# v3.net
KiCad netlist of a schematic drawn in EAGLE
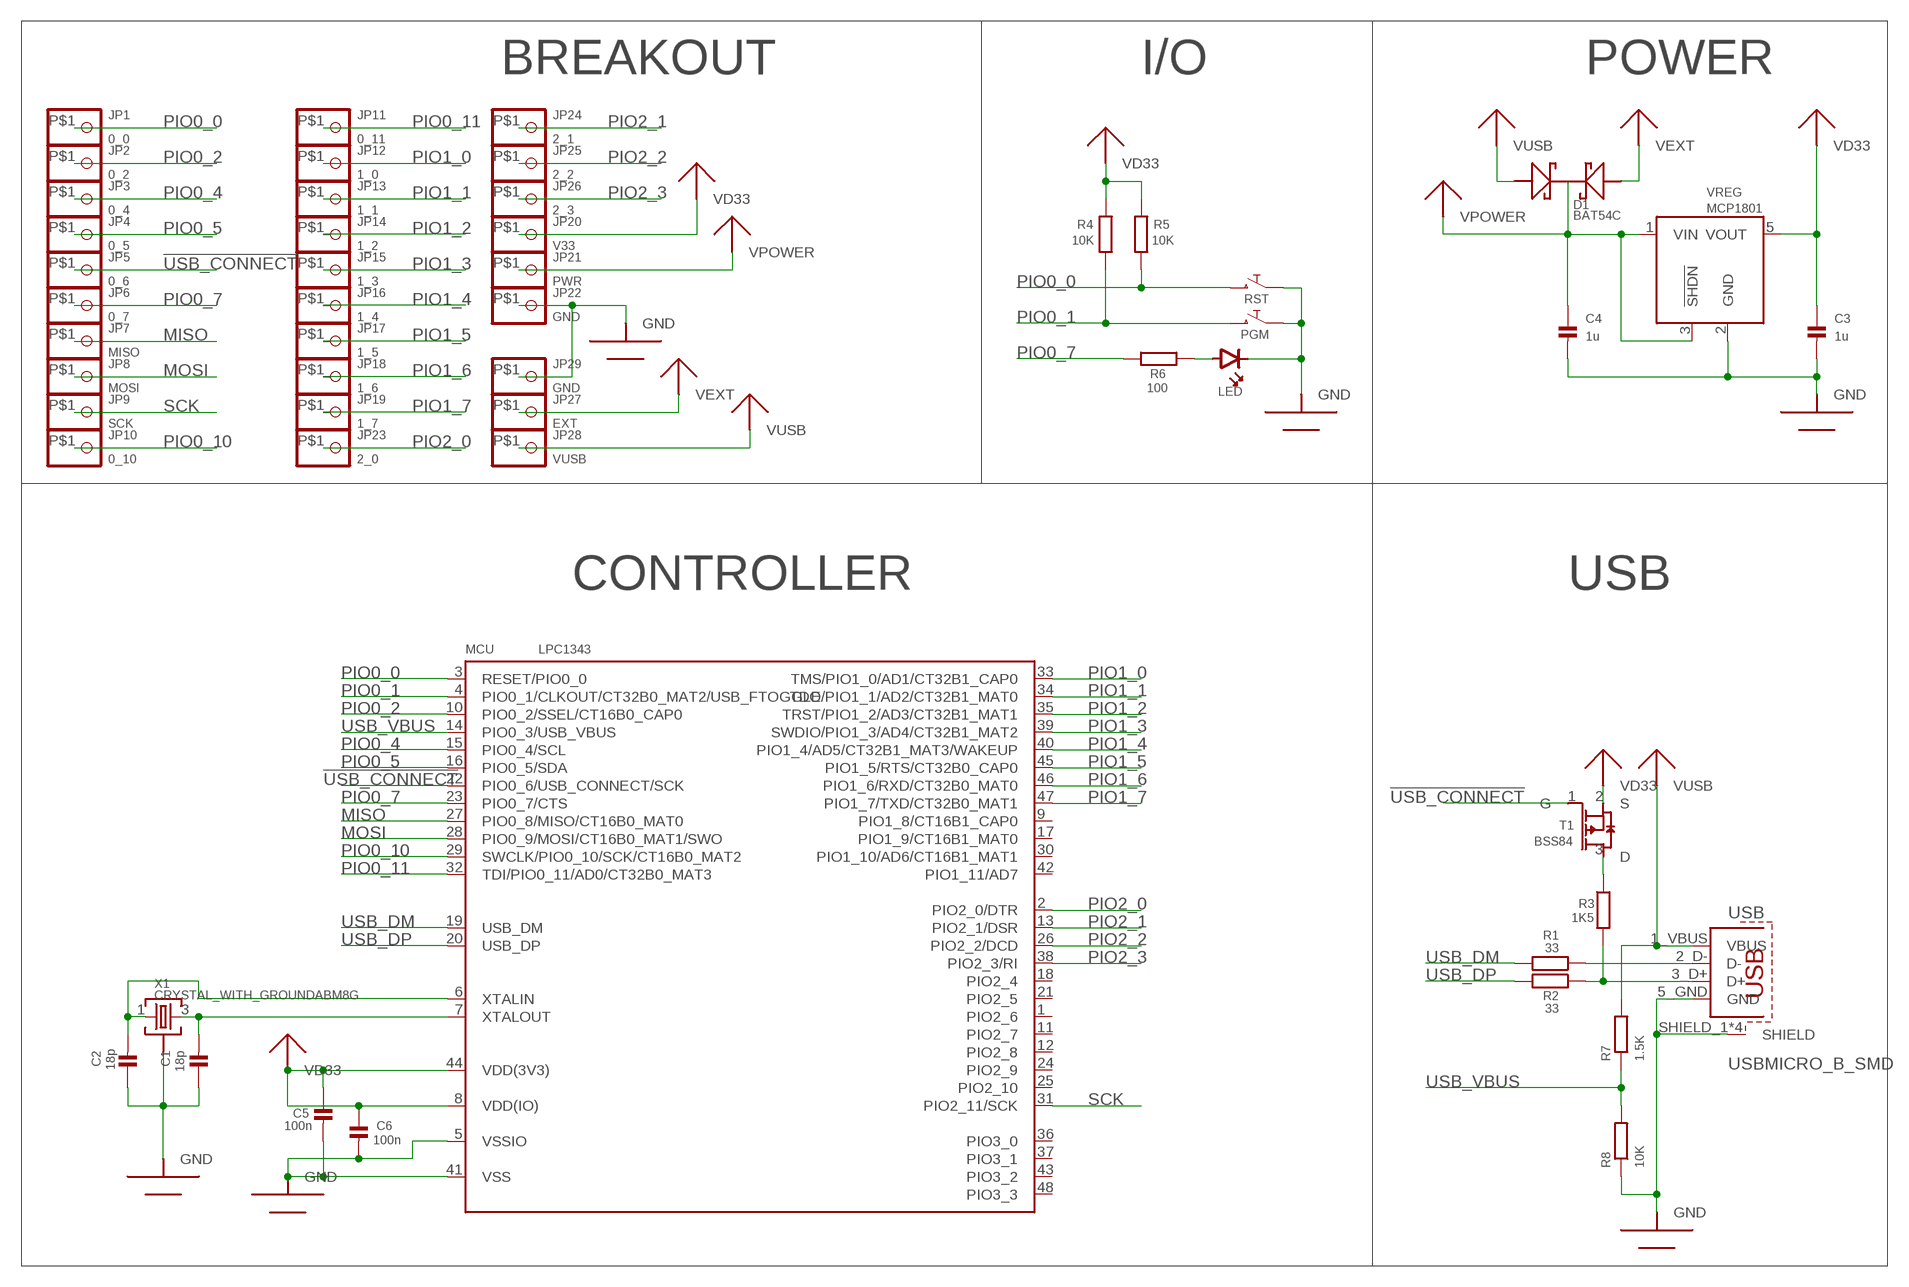
[diagram p0: schematic, sheet 1]

(export (version "E")
  (design (tool "Eeschema 10.0.6"))
  (components
    (comp (ref "C1")
      (value "18p")
      (footprint "eagle-import:0603")
      (libsource (lib "eagle-import") (part "CAP_CERAMIC0603"))
    )
    (comp (ref "C2")
      (value "18p")
      (footprint "eagle-import:0603")
      (libsource (lib "eagle-import") (part "CAP_CERAMIC0603"))
    )
    (comp (ref "C3")
      (value "1u")
      (footprint "eagle-import:0603")
      (libsource (lib "eagle-import") (part "CAP_CERAMIC0603"))
    )
    (comp (ref "C4")
      (value "1u")
      (footprint "eagle-import:0603")
      (libsource (lib "eagle-import") (part "CAP_CERAMIC0603"))
    )
    (comp (ref "C5")
      (value "100n")
      (footprint "eagle-import:0603")
      (libsource (lib "eagle-import") (part "CAP_CERAMIC0603"))
    )
    (comp (ref "C6")
      (value "100n")
      (footprint "eagle-import:0603")
      (libsource (lib "eagle-import") (part "CAP_CERAMIC0603"))
    )
    (comp (ref "D1")
      (value "BAT54C")
      (footprint "eagle-import:SOT323")
      (libsource (lib "eagle-import") (part "BAT54C"))
    )
    (comp (ref "JP1")
      (value "0_0")
      (footprint "eagle-import:PCB_MEDIUM_RECT_PAD")
      (libsource (lib "eagle-import") (part "HEADER-1X1SMD_MEDIUM"))
    )
    (comp (ref "JP2")
      (value "0_2")
      (footprint "eagle-import:PCB_MEDIUM_RECT_PAD")
      (libsource (lib "eagle-import") (part "HEADER-1X1SMD_MEDIUM"))
    )
    (comp (ref "JP3")
      (value "0_4")
      (footprint "eagle-import:PCB_MEDIUM_RECT_PAD")
      (libsource (lib "eagle-import") (part "HEADER-1X1SMD_MEDIUM"))
    )
    (comp (ref "JP4")
      (value "0_5")
      (footprint "eagle-import:PCB_MEDIUM_RECT_PAD")
      (libsource (lib "eagle-import") (part "HEADER-1X1SMD_MEDIUM"))
    )
    (comp (ref "JP5")
      (value "0_6")
      (footprint "eagle-import:PCB_MEDIUM_RECT_PAD")
      (libsource (lib "eagle-import") (part "HEADER-1X1SMD_MEDIUM"))
    )
    (comp (ref "JP6")
      (value "0_7")
      (footprint "eagle-import:PCB_MEDIUM_RECT_PAD")
      (libsource (lib "eagle-import") (part "HEADER-1X1SMD_MEDIUM"))
    )
    (comp (ref "JP7")
      (value "MISO")
      (footprint "eagle-import:PCB_MEDIUM_RECT_PAD")
      (libsource (lib "eagle-import") (part "HEADER-1X1SMD_MEDIUM"))
    )
    (comp (ref "JP8")
      (value "MOSI")
      (footprint "eagle-import:PCB_MEDIUM_RECT_PAD")
      (libsource (lib "eagle-import") (part "HEADER-1X1SMD_MEDIUM"))
    )
    (comp (ref "JP9")
      (value "SCK")
      (footprint "eagle-import:PCB_MEDIUM_RECT_PAD")
      (libsource (lib "eagle-import") (part "HEADER-1X1SMD_MEDIUM"))
    )
    (comp (ref "JP10")
      (value "0_10")
      (footprint "eagle-import:PCB_MEDIUM_RECT_PAD")
      (libsource (lib "eagle-import") (part "HEADER-1X1SMD_MEDIUM"))
    )
    (comp (ref "JP11")
      (value "0_11")
      (footprint "eagle-import:PCB_MEDIUM_RECT_PAD")
      (libsource (lib "eagle-import") (part "HEADER-1X1SMD_MEDIUM"))
    )
    (comp (ref "JP12")
      (value "1_0")
      (footprint "eagle-import:PCB_MEDIUM_RECT_PAD")
      (libsource (lib "eagle-import") (part "HEADER-1X1SMD_MEDIUM"))
    )
    (comp (ref "JP13")
      (value "1_1")
      (footprint "eagle-import:PCB_MEDIUM_RECT_PAD")
      (libsource (lib "eagle-import") (part "HEADER-1X1SMD_MEDIUM"))
    )
    (comp (ref "JP14")
      (value "1_2")
      (footprint "eagle-import:PCB_MEDIUM_RECT_PAD")
      (libsource (lib "eagle-import") (part "HEADER-1X1SMD_MEDIUM"))
    )
    (comp (ref "JP15")
      (value "1_3")
      (footprint "eagle-import:PCB_MEDIUM_RECT_PAD")
      (libsource (lib "eagle-import") (part "HEADER-1X1SMD_MEDIUM"))
    )
    (comp (ref "JP16")
      (value "1_4")
      (footprint "eagle-import:PCB_MEDIUM_RECT_PAD")
      (libsource (lib "eagle-import") (part "HEADER-1X1SMD_MEDIUM"))
    )
    (comp (ref "JP17")
      (value "1_5")
      (footprint "eagle-import:PCB_MEDIUM_RECT_PAD")
      (libsource (lib "eagle-import") (part "HEADER-1X1SMD_MEDIUM"))
    )
    (comp (ref "JP18")
      (value "1_6")
      (footprint "eagle-import:PCB_MEDIUM_RECT_PAD")
      (libsource (lib "eagle-import") (part "HEADER-1X1SMD_MEDIUM"))
    )
    (comp (ref "JP19")
      (value "1_7")
      (footprint "eagle-import:PCB_MEDIUM_RECT_PAD")
      (libsource (lib "eagle-import") (part "HEADER-1X1SMD_MEDIUM"))
    )
    (comp (ref "JP20")
      (value "V33")
      (footprint "eagle-import:PCB_MEDIUM_RECT_PAD")
      (libsource (lib "eagle-import") (part "HEADER-1X1SMD_MEDIUM"))
    )
    (comp (ref "JP21")
      (value "PWR")
      (footprint "eagle-import:PCB_MEDIUM_RECT_PAD")
      (libsource (lib "eagle-import") (part "HEADER-1X1SMD_MEDIUM"))
    )
    (comp (ref "JP22")
      (value "GND")
      (footprint "eagle-import:PCB_MEDIUM_RECT_PAD")
      (libsource (lib "eagle-import") (part "HEADER-1X1SMD_MEDIUM"))
    )
    (comp (ref "JP23")
      (value "2_0")
      (footprint "eagle-import:PCB_MEDIUM_RECT_PAD")
      (libsource (lib "eagle-import") (part "HEADER-1X1SMD_MEDIUM"))
    )
    (comp (ref "JP24")
      (value "2_1")
      (footprint "eagle-import:PCB_MEDIUM_RECT_PAD")
      (libsource (lib "eagle-import") (part "HEADER-1X1SMD_MEDIUM"))
    )
    (comp (ref "JP25")
      (value "2_2")
      (footprint "eagle-import:PCB_MEDIUM_RECT_PAD")
      (libsource (lib "eagle-import") (part "HEADER-1X1SMD_MEDIUM"))
    )
    (comp (ref "JP26")
      (value "2_3")
      (footprint "eagle-import:PCB_MEDIUM_RECT_PAD")
      (libsource (lib "eagle-import") (part "HEADER-1X1SMD_MEDIUM"))
    )
    (comp (ref "JP27")
      (value "EXT")
      (footprint "eagle-import:PCB_LARGER_RECT_PAD")
      (libsource (lib "eagle-import") (part "HEADER-1X1SMD_LARGER"))
    )
    (comp (ref "JP28")
      (value "VUSB")
      (footprint "eagle-import:PCB_LARGER_RECT_PAD")
      (libsource (lib "eagle-import") (part "HEADER-1X1SMD_LARGER"))
    )
    (comp (ref "JP29")
      (value "GND")
      (footprint "eagle-import:PCB_LARGER_RECT_PAD")
      (libsource (lib "eagle-import") (part "HEADER-1X1SMD_LARGER"))
    )
    (comp (ref "LED")
      (value "LED0603")
      (footprint "eagle-import:0603_POLAR")
      (libsource (lib "eagle-import") (part "LED0603"))
    )
    (comp (ref "MCU")
      (value "LPC1343")
      (footprint "eagle-import:LQFP48")
      (libsource (lib "eagle-import") (part "LPC1343_QFP"))
    )
    (comp (ref "PGM")
      (value "PUSHBUTTONKMR2XX")
      (footprint "eagle-import:CK-KMR2")
      (libsource (lib "eagle-import") (part "PUSHBUTTONKMR2XX"))
    )
    (comp (ref "R1")
      (value "33")
      (footprint "eagle-import:0603")
      (libsource (lib "eagle-import") (part "R-EU_0603"))
    )
    (comp (ref "R2")
      (value "33")
      (footprint "eagle-import:0603")
      (libsource (lib "eagle-import") (part "R-EU_0603"))
    )
    (comp (ref "R3")
      (value "1K5")
      (footprint "eagle-import:0603")
      (libsource (lib "eagle-import") (part "R-EU_0603"))
    )
    (comp (ref "R4")
      (value "10K")
      (footprint "eagle-import:0603")
      (libsource (lib "eagle-import") (part "R-EU_0603"))
    )
    (comp (ref "R5")
      (value "10K")
      (footprint "eagle-import:0603")
      (libsource (lib "eagle-import") (part "R-EU_0603"))
    )
    (comp (ref "R6")
      (value "100")
      (footprint "eagle-import:0603")
      (libsource (lib "eagle-import") (part "R-EU_0603"))
    )
    (comp (ref "R7")
      (value "1.5K")
      (footprint "eagle-import:0603")
      (libsource (lib "eagle-import") (part "R-EU_0603"))
    )
    (comp (ref "R8")
      (value "10K")
      (footprint "eagle-import:0603")
      (libsource (lib "eagle-import") (part "R-EU_0603"))
    )
    (comp (ref "RST")
      (value "PUSHBUTTONKMR2XX")
      (footprint "eagle-import:CK-KMR2")
      (libsource (lib "eagle-import") (part "PUSHBUTTONKMR2XX"))
    )
    (comp (ref "T1")
      (value "BSS84")
      (footprint "eagle-import:SOT23")
      (libsource (lib "eagle-import") (part "PMOS_ENH"))
    )
    (comp (ref "USB")
      (value "USBMICRO_B_SMD")
      (footprint "eagle-import:MICRO_USB_B_SMD")
      (libsource (lib "eagle-import") (part "USBMICRO_B_SMD"))
    )
    (comp (ref "VREG")
      (value "MCP1801")
      (footprint "eagle-import:SOT-23-5")
      (libsource (lib "eagle-import") (part "MCP180XSOT-23-5"))
    )
    (comp (ref "X1")
      (value "CRYSTAL_WITH_GROUNDABM8G")
      (footprint "eagle-import:ABM8G")
      (libsource (lib "eagle-import") (part "CRYSTAL_WITH_GROUNDABM8G"))
    )
  )
  (nets
    (net (code "1") (name "/MISO") (class "Default")
      (node (ref "JP7") (pin "P$1") (pinfunction "1_P$1") (pintype "passive"))
      (node (ref "MCU") (pin "27") (pinfunction "PIO0_8/MISO/CT16B0_MAT0_27") (pintype "bidirectional"))
    )
    (net (code "2") (name "/MOSI") (class "Default")
      (node (ref "JP8") (pin "P$1") (pinfunction "1_P$1") (pintype "passive"))
      (node (ref "MCU") (pin "28") (pinfunction "PIO0_9/MOSI/CT16B0_MAT1/SWO_28") (pintype "bidirectional"))
    )
    (net (code "3") (name "/PIO0_0") (class "Default")
      (node (ref "JP1") (pin "P$1") (pinfunction "1_P$1") (pintype "passive"))
      (node (ref "MCU") (pin "3") (pinfunction "RESET/PIO0_0_3") (pintype "bidirectional"))
      (node (ref "R5") (pin "1") (pinfunction "1_1") (pintype "passive"))
      (node (ref "RST") (pin "P$3") (pinfunction "2_P$3") (pintype "bidirectional"))
      (node (ref "RST") (pin "P$4") (pinfunction "2_P$4") (pintype "bidirectional"))
    )
    (net (code "4") (name "/PIO0_1") (class "Default")
      (node (ref "MCU") (pin "4") (pinfunction "PIO0_1/CLKOUT/CT32B0_MAT2/USB_FTOGGLE_4") (pintype "bidirectional"))
      (node (ref "PGM") (pin "P$3") (pinfunction "2_P$3") (pintype "bidirectional"))
      (node (ref "PGM") (pin "P$4") (pinfunction "2_P$4") (pintype "bidirectional"))
      (node (ref "R4") (pin "1") (pinfunction "1_1") (pintype "passive"))
    )
    (net (code "5") (name "/PIO0_2") (class "Default")
      (node (ref "JP2") (pin "P$1") (pinfunction "1_P$1") (pintype "passive"))
      (node (ref "MCU") (pin "10") (pinfunction "PIO0_2/SSEL/CT16B0_CAP0_10") (pintype "bidirectional"))
    )
    (net (code "6") (name "/PIO0_4") (class "Default")
      (node (ref "JP3") (pin "P$1") (pinfunction "1_P$1") (pintype "passive"))
      (node (ref "MCU") (pin "15") (pinfunction "PIO0_4/SCL_15") (pintype "bidirectional"))
    )
    (net (code "7") (name "/PIO0_5") (class "Default")
      (node (ref "JP4") (pin "P$1") (pinfunction "1_P$1") (pintype "passive"))
      (node (ref "MCU") (pin "16") (pinfunction "PIO0_5/SDA_16") (pintype "bidirectional"))
    )
    (net (code "8") (name "/PIO0_7") (class "Default")
      (node (ref "JP6") (pin "P$1") (pinfunction "1_P$1") (pintype "passive"))
      (node (ref "MCU") (pin "23") (pinfunction "PIO0_7/CTS_23") (pintype "bidirectional"))
      (node (ref "R6") (pin "2") (pinfunction "2_2") (pintype "passive"))
    )
    (net (code "9") (name "/PIO0_10") (class "Default")
      (node (ref "JP10") (pin "P$1") (pinfunction "1_P$1") (pintype "passive"))
      (node (ref "MCU") (pin "29") (pinfunction "SWCLK/PIO0_10/SCK/CT16B0_MAT2_29") (pintype "bidirectional"))
    )
    (net (code "10") (name "/PIO0_11") (class "Default")
      (node (ref "JP11") (pin "P$1") (pinfunction "1_P$1") (pintype "passive"))
      (node (ref "MCU") (pin "32") (pinfunction "TDI/PIO0_11/AD0/CT32B0_MAT3_32") (pintype "bidirectional"))
    )
    (net (code "11") (name "/PIO1_0") (class "Default")
      (node (ref "JP12") (pin "P$1") (pinfunction "1_P$1") (pintype "passive"))
      (node (ref "MCU") (pin "33") (pinfunction "TMS/PIO1_0/AD1/CT32B1_CAP0_33") (pintype "bidirectional"))
    )
    (net (code "12") (name "/PIO1_1") (class "Default")
      (node (ref "JP13") (pin "P$1") (pinfunction "1_P$1") (pintype "passive"))
      (node (ref "MCU") (pin "34") (pinfunction "TDO/PIO1_1/AD2/CT32B1_MAT0_34") (pintype "bidirectional"))
    )
    (net (code "13") (name "/PIO1_2") (class "Default")
      (node (ref "JP14") (pin "P$1") (pinfunction "1_P$1") (pintype "passive"))
      (node (ref "MCU") (pin "35") (pinfunction "TRST/PIO1_2/AD3/CT32B1_MAT1_35") (pintype "bidirectional"))
    )
    (net (code "14") (name "/PIO1_3") (class "Default")
      (node (ref "JP15") (pin "P$1") (pinfunction "1_P$1") (pintype "passive"))
      (node (ref "MCU") (pin "39") (pinfunction "SWDIO/PIO1_3/AD4/CT32B1_MAT2_39") (pintype "bidirectional"))
    )
    (net (code "15") (name "/PIO1_4") (class "Default")
      (node (ref "JP16") (pin "P$1") (pinfunction "1_P$1") (pintype "passive"))
      (node (ref "MCU") (pin "40") (pinfunction "PIO1_4/AD5/CT32B1_MAT3/WAKEUP_40") (pintype "bidirectional"))
    )
    (net (code "16") (name "/PIO1_5") (class "Default")
      (node (ref "JP17") (pin "P$1") (pinfunction "1_P$1") (pintype "passive"))
      (node (ref "MCU") (pin "45") (pinfunction "PIO1_5/RTS/CT32B0_CAP0_45") (pintype "bidirectional"))
    )
    (net (code "17") (name "/PIO1_6") (class "Default")
      (node (ref "JP18") (pin "P$1") (pinfunction "1_P$1") (pintype "passive"))
      (node (ref "MCU") (pin "46") (pinfunction "PIO1_6/RXD/CT32B0_MAT0_46") (pintype "bidirectional"))
    )
    (net (code "18") (name "/PIO1_7") (class "Default")
      (node (ref "JP19") (pin "P$1") (pinfunction "1_P$1") (pintype "passive"))
      (node (ref "MCU") (pin "47") (pinfunction "PIO1_7/TXD/CT32B0_MAT1_47") (pintype "bidirectional"))
    )
    (net (code "19") (name "/PIO2_0") (class "Default")
      (node (ref "JP23") (pin "P$1") (pinfunction "1_P$1") (pintype "passive"))
      (node (ref "MCU") (pin "2") (pinfunction "PIO2_0/DTR_2") (pintype "bidirectional"))
    )
    (net (code "20") (name "/PIO2_1") (class "Default")
      (node (ref "JP24") (pin "P$1") (pinfunction "1_P$1") (pintype "passive"))
      (node (ref "MCU") (pin "13") (pinfunction "PIO2_1/DSR_13") (pintype "bidirectional"))
    )
    (net (code "21") (name "/PIO2_2") (class "Default")
      (node (ref "JP25") (pin "P$1") (pinfunction "1_P$1") (pintype "passive"))
      (node (ref "MCU") (pin "26") (pinfunction "PIO2_2/DCD_26") (pintype "bidirectional"))
    )
    (net (code "22") (name "/PIO2_3") (class "Default")
      (node (ref "JP26") (pin "P$1") (pinfunction "1_P$1") (pintype "passive"))
      (node (ref "MCU") (pin "38") (pinfunction "PIO2_3/RI_38") (pintype "bidirectional"))
    )
    (net (code "23") (name "/SCK") (class "Default")
      (node (ref "JP9") (pin "P$1") (pinfunction "1_P$1") (pintype "passive"))
      (node (ref "MCU") (pin "31") (pinfunction "PIO2_11/SCK_31") (pintype "bidirectional"))
    )
    (net (code "24") (name "/USB_DM") (class "Default")
      (node (ref "MCU") (pin "19") (pinfunction "USB_DM_19") (pintype "bidirectional"))
      (node (ref "R1") (pin "2") (pinfunction "2_2") (pintype "passive"))
    )
    (net (code "25") (name "/USB_DP") (class "Default")
      (node (ref "MCU") (pin "20") (pinfunction "USB_DP_20") (pintype "bidirectional"))
      (node (ref "R2") (pin "2") (pinfunction "2_2") (pintype "passive"))
    )
    (net (code "26") (name "/USB_VBUS") (class "Default")
      (node (ref "MCU") (pin "14") (pinfunction "PIO0_3/USB_VBUS_14") (pintype "bidirectional"))
      (node (ref "R7") (pin "1") (pinfunction "1_1") (pintype "passive"))
      (node (ref "R8") (pin "2") (pinfunction "2_2") (pintype "passive"))
    )
    (net (code "27") (name "/~{USB_CONNECT}") (class "Default")
      (node (ref "JP5") (pin "P$1") (pinfunction "1_P$1") (pintype "passive"))
      (node (ref "MCU") (pin "22") (pinfunction "PIO0_6/USB_CONNECT/SCK_22") (pintype "bidirectional"))
      (node (ref "T1") (pin "1") (pinfunction "G_1") (pintype "bidirectional"))
    )
    (net (code "28") (name "GND") (class "Default")
      (node (ref "C1") (pin "1") (pinfunction "P$1_1") (pintype "passive"))
      (node (ref "C2") (pin "1") (pinfunction "P$1_1") (pintype "passive"))
      (node (ref "C3") (pin "2") (pinfunction "P$2_2") (pintype "passive"))
      (node (ref "C4") (pin "2") (pinfunction "P$2_2") (pintype "passive"))
      (node (ref "C5") (pin "2") (pinfunction "P$2_2") (pintype "passive"))
      (node (ref "C6") (pin "2") (pinfunction "P$2_2") (pintype "passive"))
      (node (ref "JP22") (pin "P$1") (pinfunction "1_P$1") (pintype "passive"))
      (node (ref "JP29") (pin "P$1") (pinfunction "1_P$1") (pintype "passive"))
      (node (ref "LED") (pin "K") (pinfunction "CATHODE_K") (pintype "bidirectional"))
      (node (ref "MCU") (pin "41") (pinfunction "VSS_41") (pintype "power_in"))
      (node (ref "MCU") (pin "5") (pinfunction "VSSIO_5") (pintype "power_in"))
      (node (ref "PGM") (pin "P$1") (pinfunction "1_P$1") (pintype "bidirectional"))
      (node (ref "PGM") (pin "P$2") (pinfunction "1_P$2") (pintype "bidirectional"))
      (node (ref "R8") (pin "1") (pinfunction "1_1") (pintype "passive"))
      (node (ref "RST") (pin "P$1") (pinfunction "1_P$1") (pintype "bidirectional"))
      (node (ref "RST") (pin "P$2") (pinfunction "1_P$2") (pintype "bidirectional"))
      (node (ref "USB") (pin "5_GND") (pinfunction "GND_5_GND") (pintype "power_in"))
      (node (ref "USB") (pin "SHIELD_1") (pinfunction "SHIELD_SHIELD_1") (pintype "passive"))
      (node (ref "USB") (pin "SHIELD_2") (pinfunction "SHIELD_SHIELD_2") (pintype "passive"))
      (node (ref "USB") (pin "SHIELD_3") (pinfunction "SHIELD_SHIELD_3") (pintype "passive"))
      (node (ref "USB") (pin "SHIELD_4") (pinfunction "SHIELD_SHIELD_4") (pintype "passive"))
      (node (ref "VREG") (pin "2") (pinfunction "GND_2") (pintype "power_in"))
      (node (ref "X1") (pin "2") (pinfunction "GND_2") (pintype "power_in"))
      (node (ref "X1") (pin "4") (pinfunction "GND_4") (pintype "power_in"))
    )
    (net (code "29") (name "Net-(C1-P$2)") (class "Default")
      (node (ref "C1") (pin "2") (pinfunction "P$2_2") (pintype "passive"))
      (node (ref "MCU") (pin "7") (pinfunction "XTALOUT_7") (pintype "output"))
      (node (ref "X1") (pin "3") (pinfunction "2_3") (pintype "passive"))
    )
    (net (code "30") (name "Net-(C2-P$2)") (class "Default")
      (node (ref "C2") (pin "2") (pinfunction "P$2_2") (pintype "passive"))
      (node (ref "MCU") (pin "6") (pinfunction "XTALIN_6") (pintype "input"))
      (node (ref "X1") (pin "1") (pinfunction "1_1") (pintype "passive"))
    )
    (net (code "31") (name "Net-(LED-ANODE)") (class "Default")
      (node (ref "LED") (pin "A") (pinfunction "ANODE_A") (pintype "bidirectional"))
      (node (ref "R6") (pin "1") (pinfunction "1_1") (pintype "passive"))
    )
    (net (code "32") (name "Net-(T1-D)") (class "Default")
      (node (ref "R3") (pin "1") (pinfunction "1_1") (pintype "passive"))
      (node (ref "T1") (pin "3") (pinfunction "D_3") (pintype "bidirectional"))
    )
    (net (code "33") (name "Net-(USB-D+)") (class "Default")
      (node (ref "R2") (pin "1") (pinfunction "1_1") (pintype "passive"))
      (node (ref "R3") (pin "2") (pinfunction "2_2") (pintype "passive"))
      (node (ref "USB") (pin "3_D+") (pinfunction "D+_3_D+") (pintype "bidirectional"))
    )
    (net (code "34") (name "Net-(USB-D-)") (class "Default")
      (node (ref "R1") (pin "1") (pinfunction "1_1") (pintype "passive"))
      (node (ref "USB") (pin "2_D-") (pinfunction "D-_2_D-") (pintype "bidirectional"))
    )
    (net (code "35") (name "VD33") (class "Default")
      (node (ref "C3") (pin "1") (pinfunction "P$1_1") (pintype "passive"))
      (node (ref "C5") (pin "1") (pinfunction "P$1_1") (pintype "passive"))
      (node (ref "C6") (pin "1") (pinfunction "P$1_1") (pintype "passive"))
      (node (ref "JP20") (pin "P$1") (pinfunction "1_P$1") (pintype "passive"))
      (node (ref "MCU") (pin "44") (pinfunction "VDD(3V3)_44") (pintype "power_in"))
      (node (ref "MCU") (pin "8") (pinfunction "VDD(IO)_8") (pintype "power_in"))
      (node (ref "R4") (pin "2") (pinfunction "2_2") (pintype "passive"))
      (node (ref "R5") (pin "2") (pinfunction "2_2") (pintype "passive"))
      (node (ref "T1") (pin "2") (pinfunction "S_2") (pintype "bidirectional"))
      (node (ref "VREG") (pin "5") (pinfunction "VOUT_5") (pintype "power_in"))
    )
    (net (code "36") (name "VEXT") (class "Default")
      (node (ref "D1") (pin "2") (pinfunction "ANODE2_2") (pintype "bidirectional"))
      (node (ref "JP27") (pin "P$1") (pinfunction "1_P$1") (pintype "passive"))
    )
    (net (code "37") (name "VPOWER") (class "Default")
      (node (ref "C4") (pin "1") (pinfunction "P$1_1") (pintype "passive"))
      (node (ref "D1") (pin "3") (pinfunction "CATHODE_3") (pintype "bidirectional"))
      (node (ref "JP21") (pin "P$1") (pinfunction "1_P$1") (pintype "passive"))
      (node (ref "VREG") (pin "1") (pinfunction "VIN_1") (pintype "power_in"))
      (node (ref "VREG") (pin "3") (pinfunction "~{SHDN}_3") (pintype "input"))
    )
    (net (code "38") (name "VUSB") (class "Default")
      (node (ref "D1") (pin "1") (pinfunction "ANODE1_1") (pintype "bidirectional"))
      (node (ref "JP28") (pin "P$1") (pinfunction "1_P$1") (pintype "passive"))
      (node (ref "R7") (pin "2") (pinfunction "2_2") (pintype "passive"))
      (node (ref "USB") (pin "1_VBUS") (pinfunction "VBUS_1_VBUS") (pintype "power_in"))
    )
    (net (code "39") (name "unconnected-(MCU-PIO1_8{slash}CT16B1_CAP0-Pad9)") (class "Default")
      (node (ref "MCU") (pin "9") (pinfunction "PIO1_8/CT16B1_CAP0_9") (pintype "bidirectional"))
    )
    (net (code "40") (name "unconnected-(MCU-PIO1_9{slash}CT16B1_MAT0-Pad17)") (class "Default")
      (node (ref "MCU") (pin "17") (pinfunction "PIO1_9/CT16B1_MAT0_17") (pintype "bidirectional"))
    )
    (net (code "41") (name "unconnected-(MCU-PIO1_10{slash}AD6{slash}CT16B1_MAT1-Pad30)") (class "Default")
      (node (ref "MCU") (pin "30") (pinfunction "PIO1_10/AD6/CT16B1_MAT1_30") (pintype "bidirectional"))
    )
    (net (code "42") (name "unconnected-(MCU-PIO1_11{slash}AD7-Pad42)") (class "Default")
      (node (ref "MCU") (pin "42") (pinfunction "PIO1_11/AD7_42") (pintype "bidirectional"))
    )
    (net (code "43") (name "unconnected-(MCU-PIO2_4-Pad18)") (class "Default")
      (node (ref "MCU") (pin "18") (pinfunction "PIO2_4_18") (pintype "bidirectional"))
    )
    (net (code "44") (name "unconnected-(MCU-PIO2_5-Pad21)") (class "Default")
      (node (ref "MCU") (pin "21") (pinfunction "PIO2_5_21") (pintype "bidirectional"))
    )
    (net (code "45") (name "unconnected-(MCU-PIO2_6-Pad1)") (class "Default")
      (node (ref "MCU") (pin "1") (pinfunction "PIO2_6_1") (pintype "bidirectional"))
    )
    (net (code "46") (name "unconnected-(MCU-PIO2_7-Pad11)") (class "Default")
      (node (ref "MCU") (pin "11") (pinfunction "PIO2_7_11") (pintype "bidirectional"))
    )
    (net (code "47") (name "unconnected-(MCU-PIO2_8-Pad12)") (class "Default")
      (node (ref "MCU") (pin "12") (pinfunction "PIO2_8_12") (pintype "bidirectional"))
    )
    (net (code "48") (name "unconnected-(MCU-PIO2_9-Pad24)") (class "Default")
      (node (ref "MCU") (pin "24") (pinfunction "PIO2_9_24") (pintype "bidirectional"))
    )
    (net (code "49") (name "unconnected-(MCU-PIO2_10-Pad25)") (class "Default")
      (node (ref "MCU") (pin "25") (pinfunction "PIO2_10_25") (pintype "bidirectional"))
    )
    (net (code "50") (name "unconnected-(MCU-PIO3_0-Pad36)") (class "Default")
      (node (ref "MCU") (pin "36") (pinfunction "PIO3_0_36") (pintype "bidirectional"))
    )
    (net (code "51") (name "unconnected-(MCU-PIO3_1-Pad37)") (class "Default")
      (node (ref "MCU") (pin "37") (pinfunction "PIO3_1_37") (pintype "bidirectional"))
    )
    (net (code "52") (name "unconnected-(MCU-PIO3_2-Pad43)") (class "Default")
      (node (ref "MCU") (pin "43") (pinfunction "PIO3_2_43") (pintype "bidirectional"))
    )
    (net (code "53") (name "unconnected-(MCU-PIO3_3-Pad48)") (class "Default")
      (node (ref "MCU") (pin "48") (pinfunction "PIO3_3_48") (pintype "bidirectional"))
    )
  )
)
